# 14_PM8916_CONTROL_CLOCK.net
KiCad netlist of a schematic drawn in Altium Designer
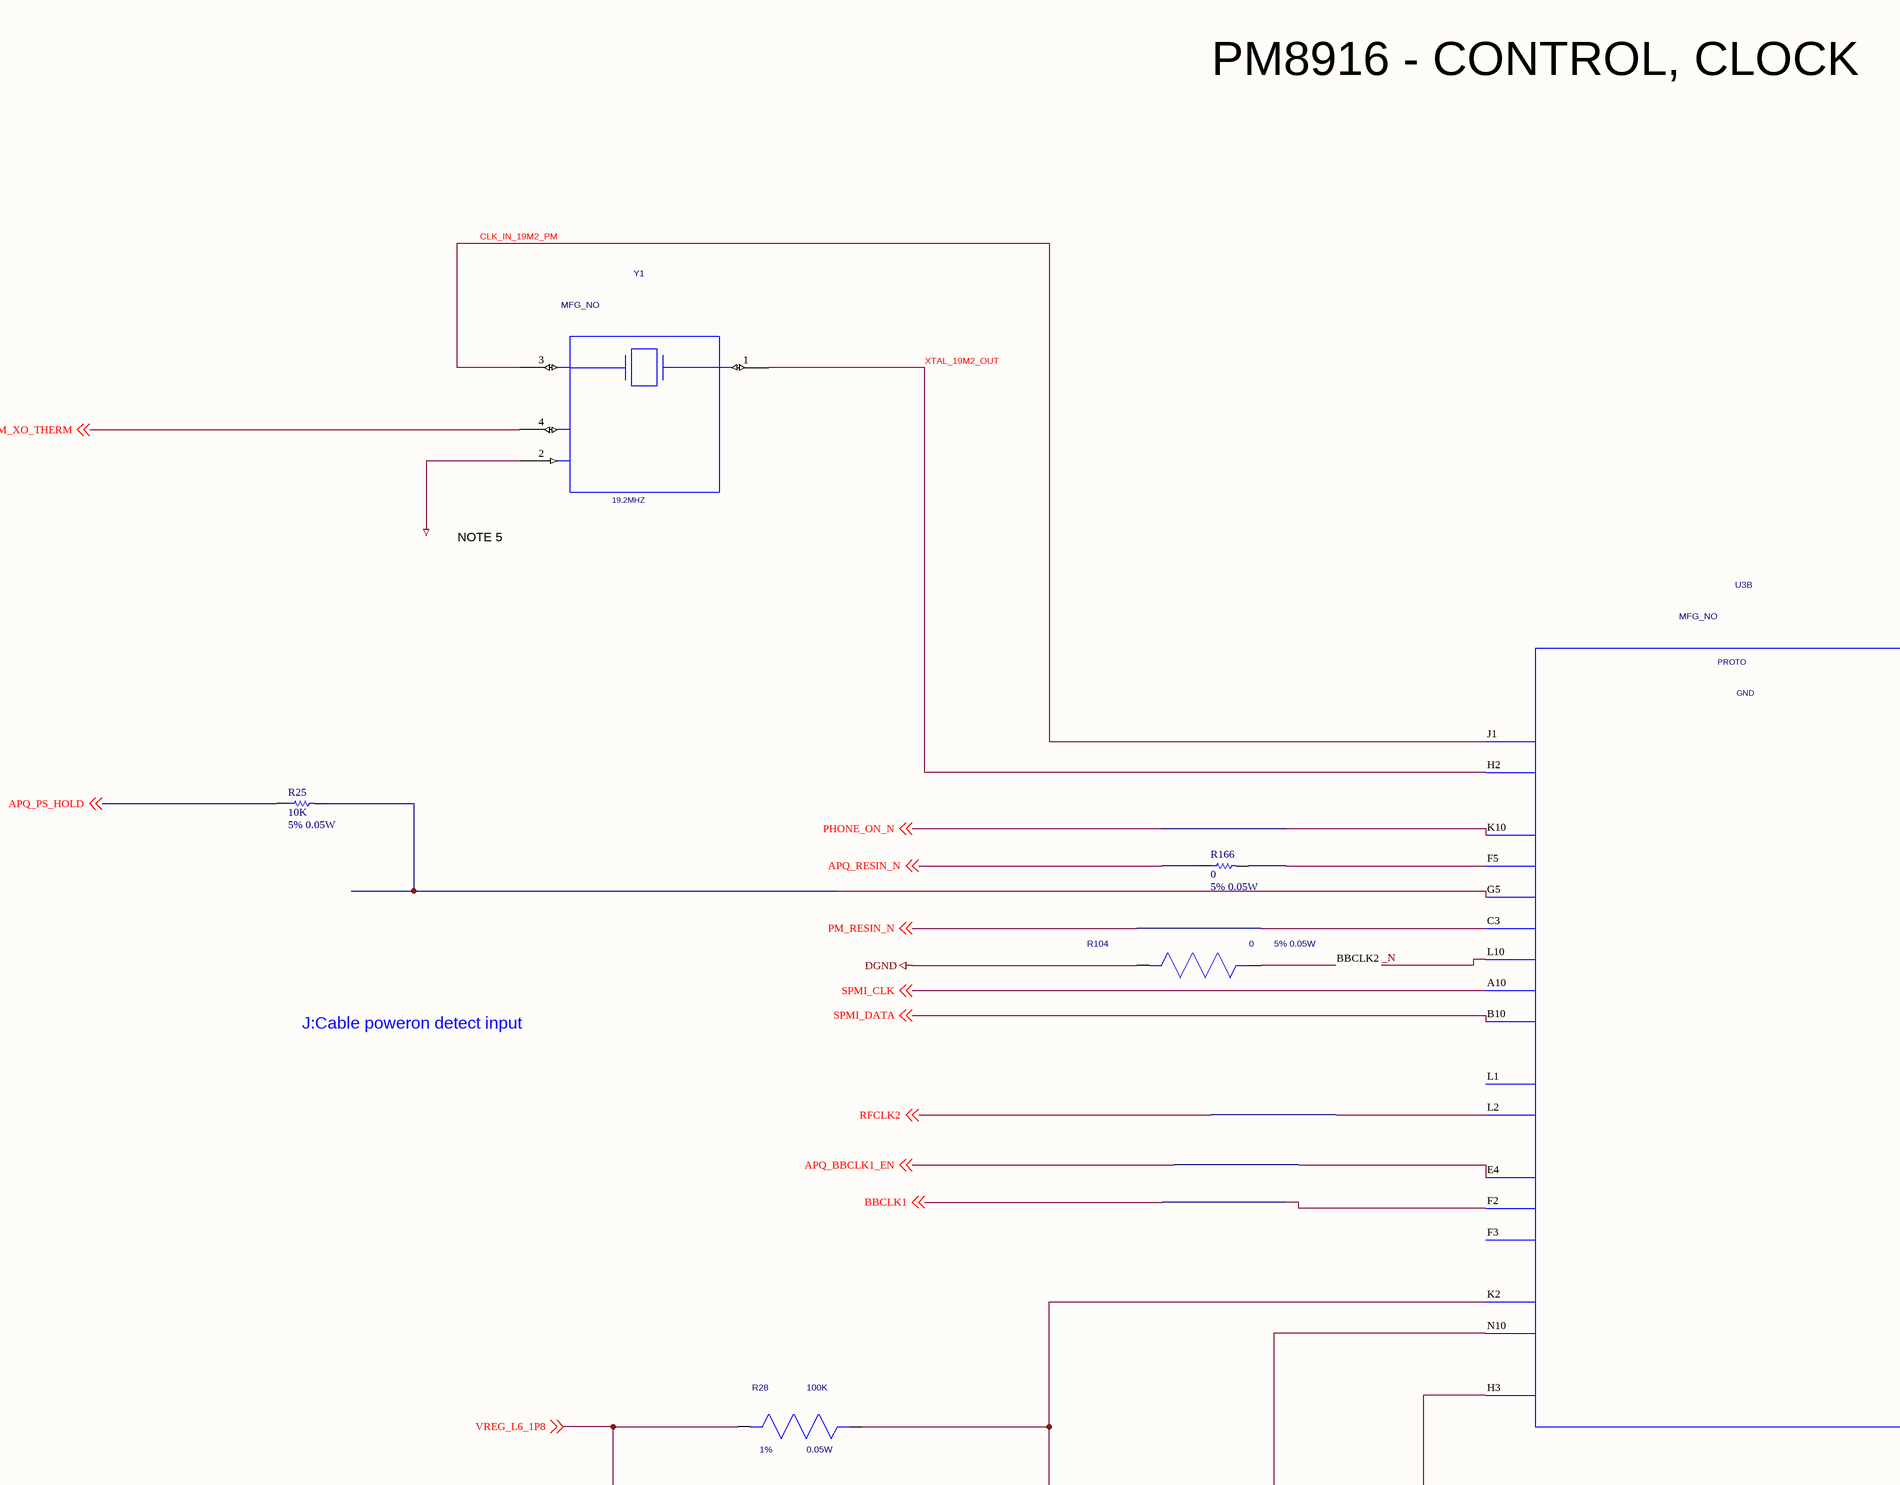
[diagram p0: 14 PM8916_CONTROL CLOCK.SchDoc, top left]
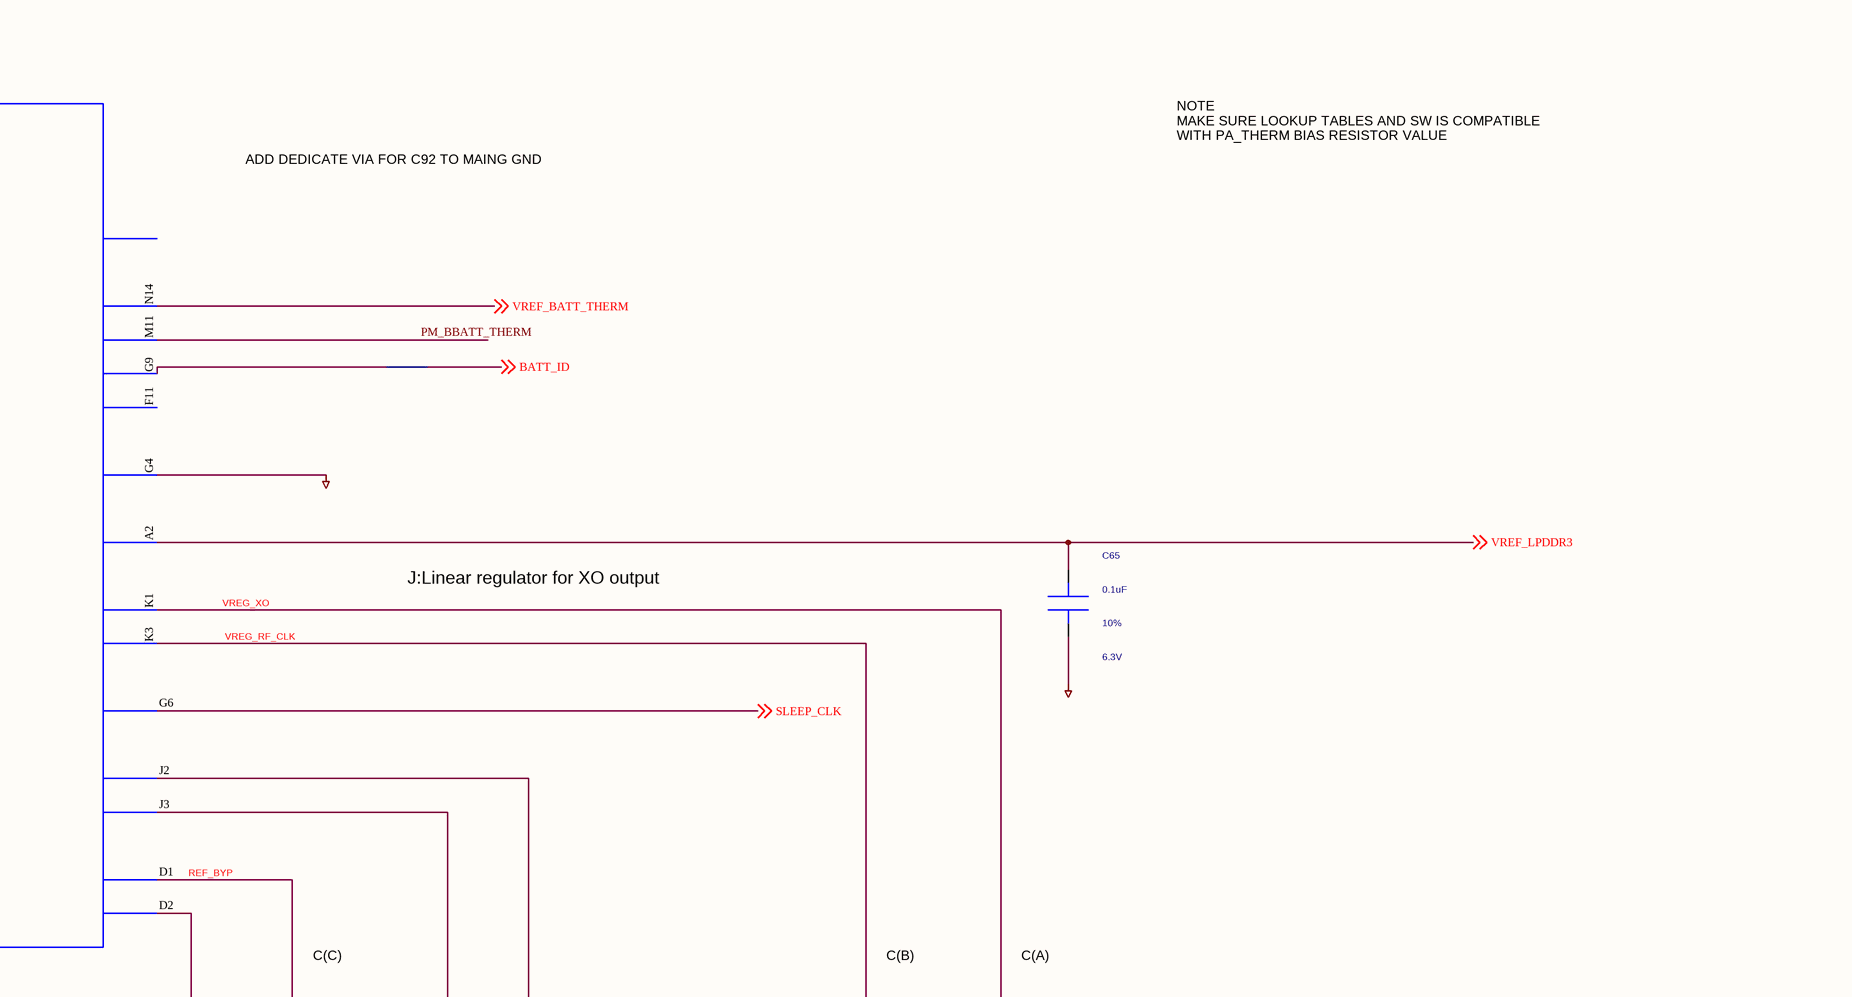
[diagram p1: 14 PM8916_CONTROL CLOCK.SchDoc, top right]
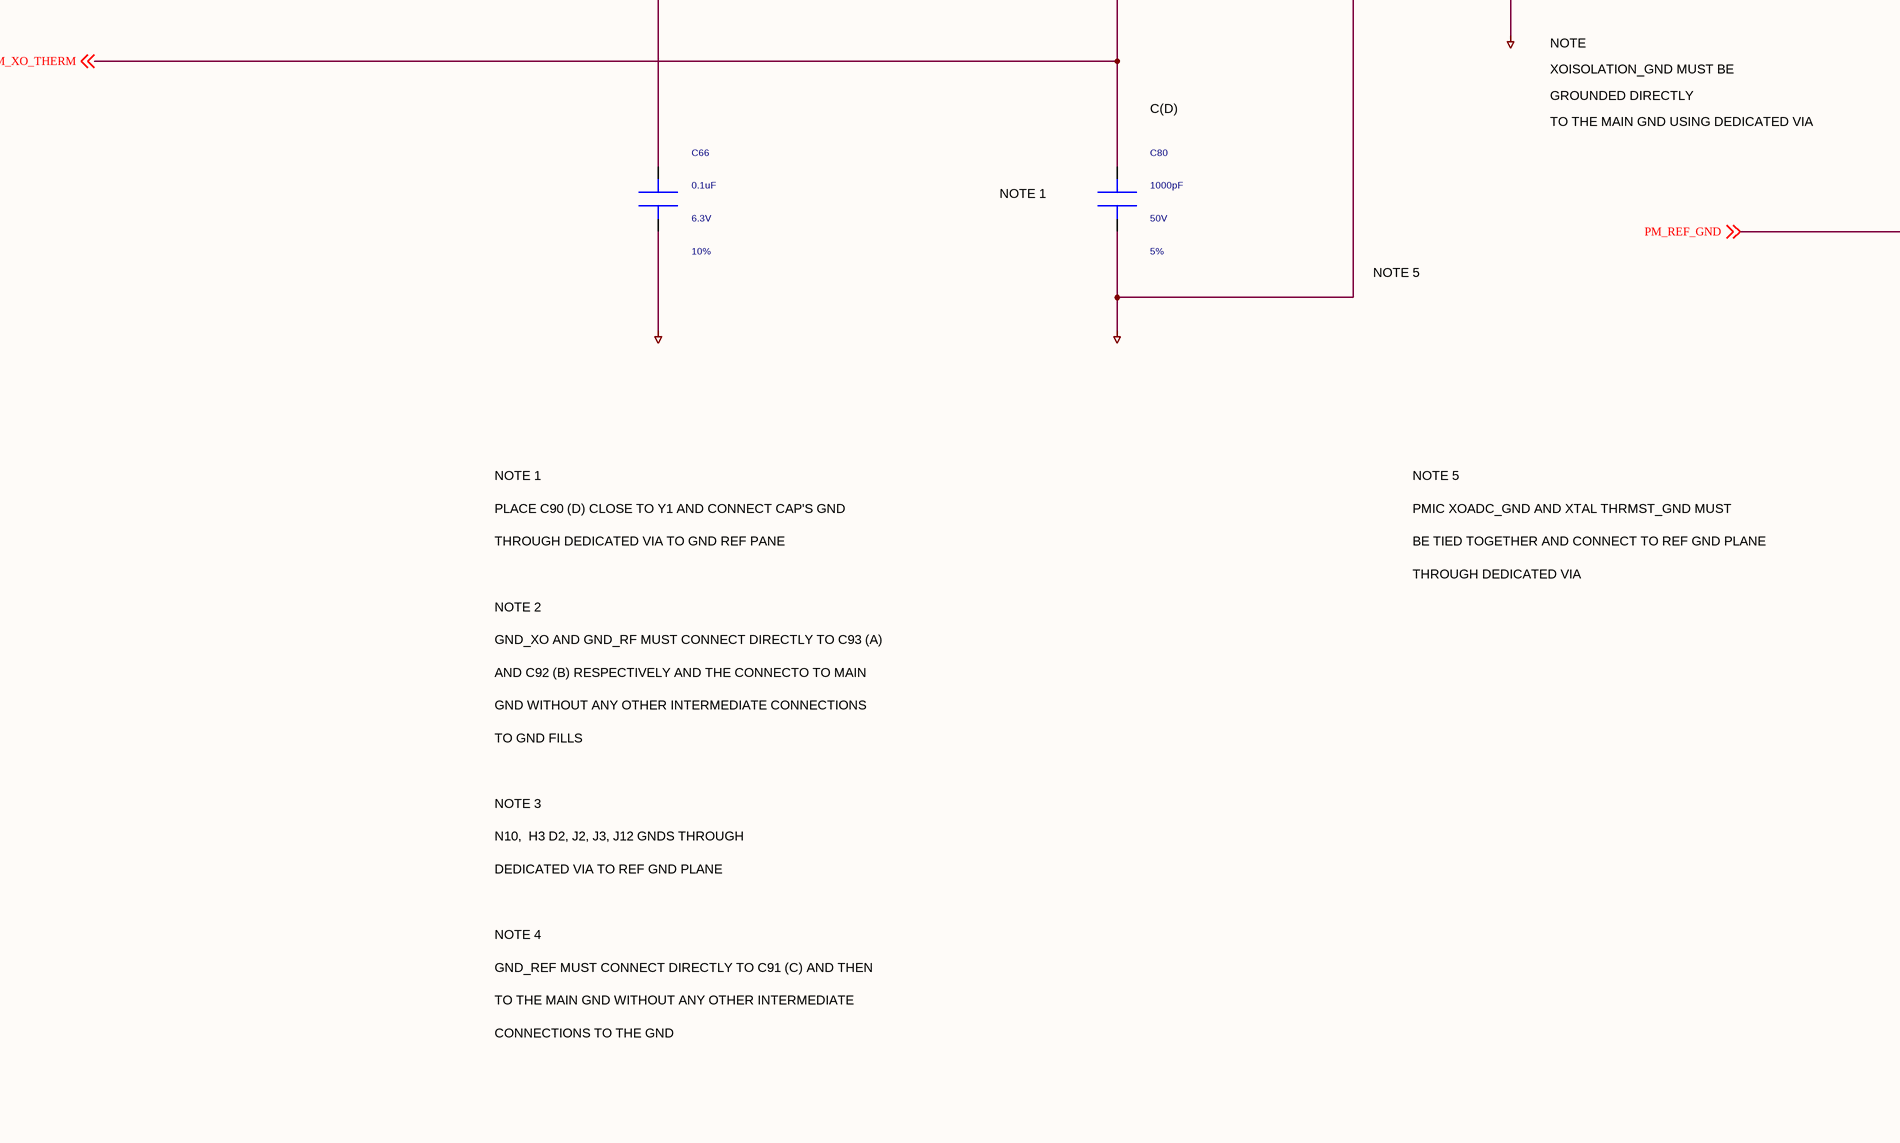
[diagram p2: 14 PM8916_CONTROL CLOCK.SchDoc, bottom left]
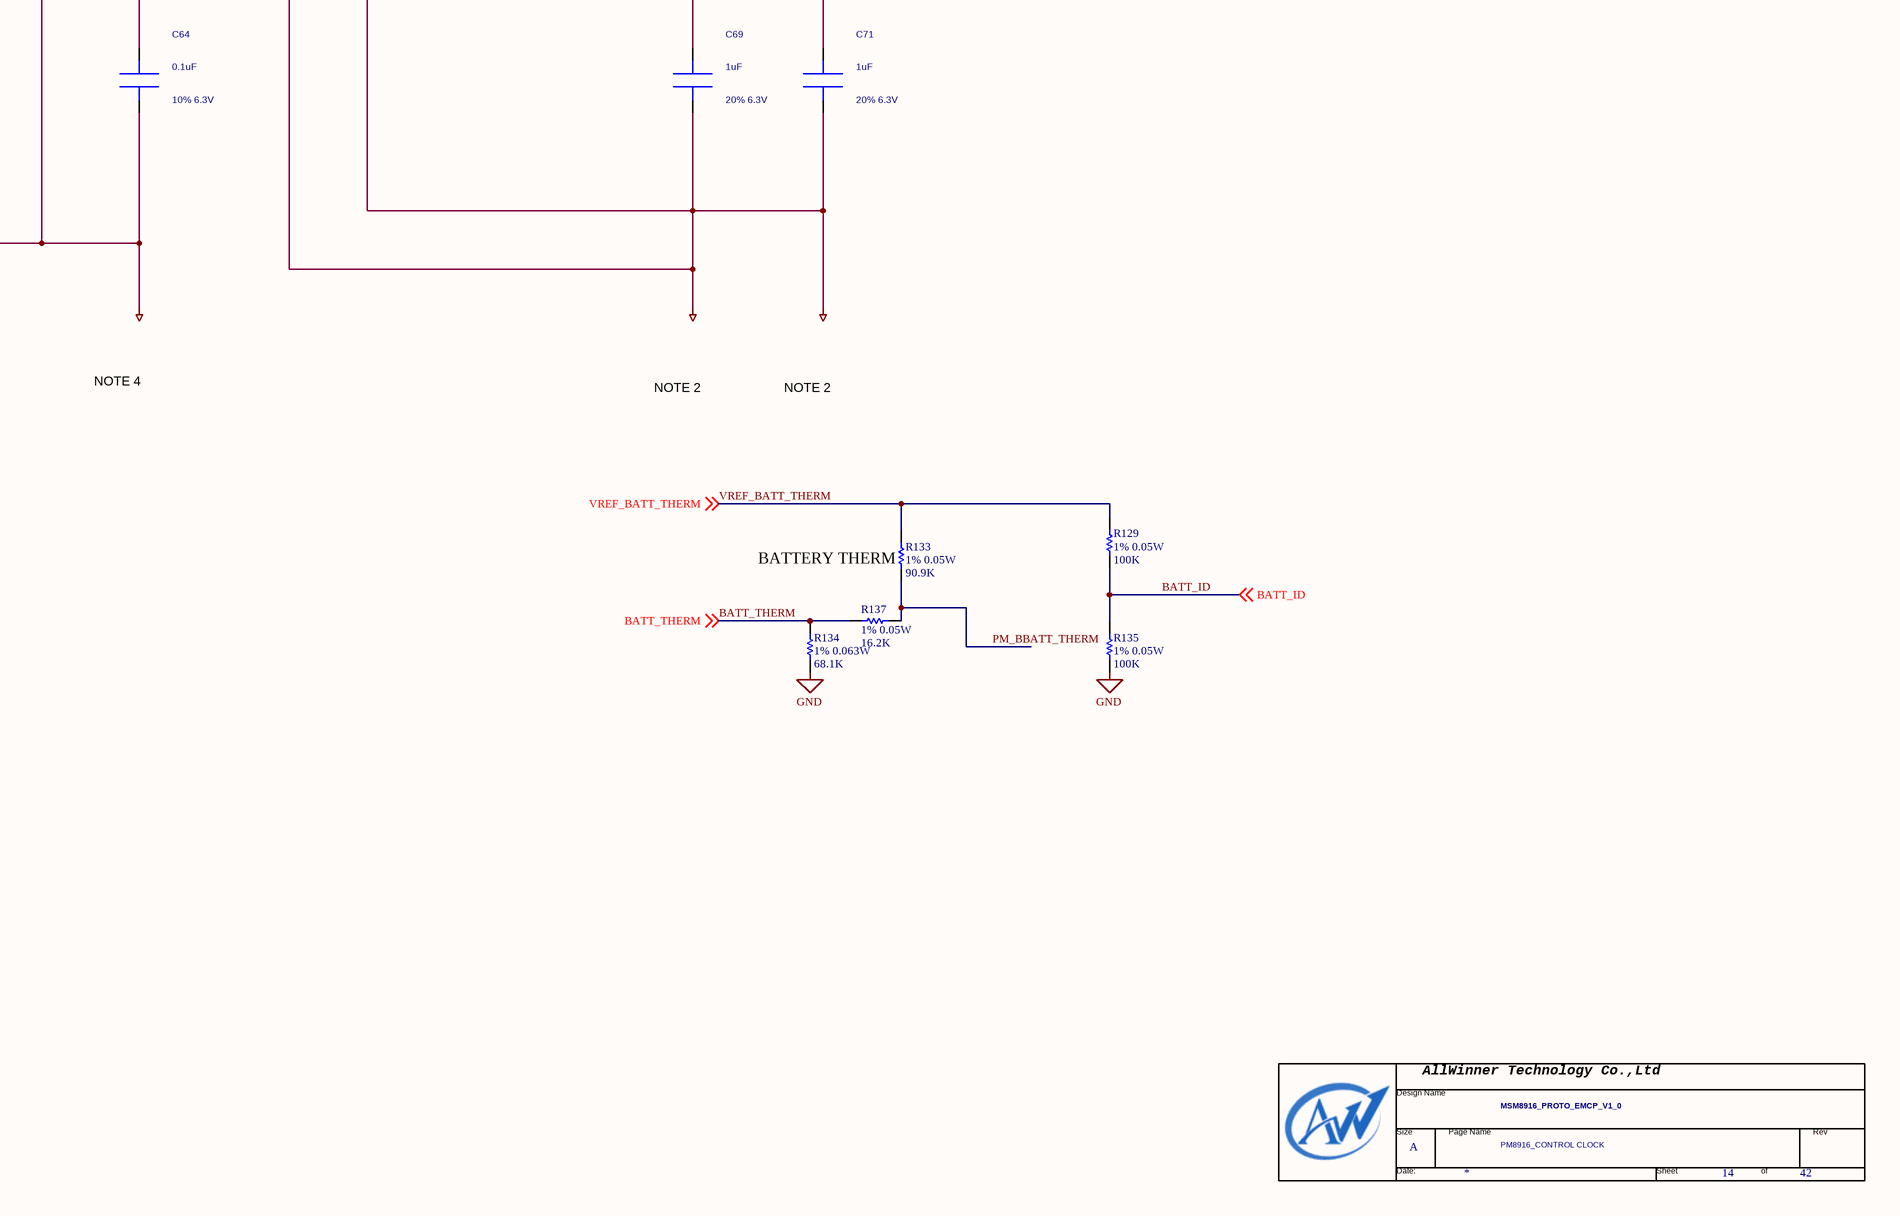
[diagram p3: 14 PM8916_CONTROL CLOCK.SchDoc, bottom right]

(export (version "E")
  (design (tool "Eeschema 10.0.6"))
  (components
    (comp (ref "C64")
      (value "0.1uF")
      (footprint "c0402")
      (fields (field (name "TOLERANCE") "10% 6.3V") (field (name "PART_NUMBER") "MCN_NO"))
      (libsource (lib "MSM8916_DRAM_PMIC_REF_Library") (part "CAP"))
    )
    (comp (ref "C65")
      (value "0.1uF")
      (footprint "c0402")
      (fields
        (field (name "VOLT") "6.3V")
        (field (name "TOLERANCE") "10%")
        (field (name "PART_NUMBER") "MCN_NO")
      )
      (libsource (lib "MSM8916_DRAM_PMIC_REF_Library") (part "CAP"))
    )
    (comp (ref "C66")
      (value "0.1uF")
      (footprint "c0402")
      (fields
        (field (name "VOLT") "10%")
        (field (name "TOLERANCE") "6.3V")
        (field (name "PART_NUMBER") "MCN_NO")
      )
      (libsource (lib "MSM8916_DRAM_PMIC_REF_Library") (part "CAP"))
    )
    (comp (ref "C69")
      (value "1uF")
      (footprint "c0402")
      (fields (field (name "TOLERANCE") "20% 6.3V") (field (name "PART_NUMBER") "MCN_NO"))
      (libsource (lib "MSM8916_DRAM_PMIC_REF_Library") (part "CAP"))
    )
    (comp (ref "C71")
      (value "1uF")
      (footprint "c0402")
      (fields (field (name "TOLERANCE") "20% 6.3V") (field (name "PART_NUMBER") "MCN_NO"))
      (libsource (lib "MSM8916_DRAM_PMIC_REF_Library") (part "CAP"))
    )
    (comp (ref "C80")
      (value "1000pF")
      (footprint "c0402")
      (fields
        (field (name "VOLT") "5%")
        (field (name "TOLERANCE") "50V")
        (field (name "PART_NUMBER") "MCN_NO")
      )
      (libsource (lib "MSM8916_DRAM_PMIC_REF_Library") (part "CAP"))
    )
    (comp (ref "R25")
      (value "10K")
      (footprint "r0402")
      (description "Resistor")
      (fields (field (name "ALTIUM_VALUE") "5% 0.05W") (field (name "PUBLISHER") "Altium Limited"))
      (libsource (lib "Miscellaneous Devices") (part "Res1"))
    )
    (comp (ref "R28")
      (value "100K")
      (footprint "c0402")
      (fields
        (field (name "TOLERANCE") "1%")
        (field (name "POWER") "0.05W")
        (field (name "PART_NUMBER") "MCN_NO")
      )
      (libsource (lib "MSM8916_DRAM_PMIC_REF_Library") (part "RESISTOR_Dup3"))
    )
    (comp (ref "R104")
      (value "0")
      (footprint "c0402")
      (fields
        (field (name "TOLERANCE") "?%")
        (field (name "POWER") "5% 0.05W")
        (field (name "PART_NUMBER") "MCN_NO")
      )
      (libsource (lib "MSM8916_DRAM_PMIC_REF_Library") (part "RESISTOR_Dup3"))
    )
    (comp (ref "R129")
      (value "1% 0.05W")
      (footprint "r0402")
      (description "Resistor")
      (fields (field (name "ALTIUM_VALUE") "100K") (field (name "PUBLISHER") "Altium Limited"))
      (libsource (lib "Miscellaneous Devices") (part "Res1"))
    )
    (comp (ref "R133")
      (value "1% 0.05W")
      (footprint "r0402")
      (description "Resistor")
      (fields (field (name "ALTIUM_VALUE") "90.9K") (field (name "PUBLISHER") "Altium Limited"))
      (libsource (lib "Miscellaneous Devices") (part "Res1"))
    )
    (comp (ref "R134")
      (value "1% 0.063W")
      (footprint "r0402")
      (description "Resistor")
      (fields (field (name "ALTIUM_VALUE") "68.1K") (field (name "PUBLISHER") "Altium Limited"))
      (libsource (lib "Miscellaneous Devices") (part "Res1"))
    )
    (comp (ref "R135")
      (value "1% 0.05W")
      (footprint "r0402")
      (description "Resistor")
      (fields (field (name "ALTIUM_VALUE") "100K") (field (name "PUBLISHER") "Altium Limited"))
      (libsource (lib "Miscellaneous Devices") (part "Res1"))
    )
    (comp (ref "R137")
      (value "1% 0.05W")
      (footprint "r0402")
      (description "Resistor")
      (fields (field (name "ALTIUM_VALUE") "16.2K") (field (name "PUBLISHER") "Altium Limited"))
      (libsource (lib "Miscellaneous Devices") (part "Res1"))
    )
    (comp (ref "R166")
      (value "0")
      (footprint "r0402")
      (description "Resistor")
      (fields (field (name "ALTIUM_VALUE") "5% 0.05W") (field (name "PUBLISHER") "Altium Limited"))
      (libsource (lib "Miscellaneous Devices") (part "Res1"))
    )
    (comp (ref "U3")
      (value "ASIC_PM8916")
      (footprint "PM-8916-0-176NSP-TR-00-0")
      (fields
        (field (name "SYMNAME") "GND")
        (field (name "PART_NUMBER") "MCN_NO")
        (field (name "PART_ID") "MFG_NO")
        (field (name "BLOCKID") "PROTO")
      )
      (libsource (lib "MSM8916_DRAM_PMIC_REF_Library") (part "ASIC_PM8916"))
    )
    (comp (ref "Y1")
      (value "crystal_4pin_thermistor_gnd")
      (footprint "c0402")
      (fields
        (field (name "PART_NUMBER") "MCN_NO")
        (field (name "PART_ID") "MFG_NO")
        (field (name "FREQ") "19.2MHZ")
      )
      (libsource (lib "MSM8916_DRAM_PMIC_REF_Library") (part "CRYSTAL_4PIN_THERMISTOR_GND"))
    )
  )
  (nets
    (net (code "1") (name "/CBLPWR_N") (class "Default")
      (node (ref "R104") (pin "2") (pinfunction "NEG_2") (pintype "bidirectional"))
      (node (ref "U3") (pin "L10") (pinfunction "CBLPWR*_L10") (pintype "bidirectional"))
    )
    (net (code "2") (name "/CLK_IN_19M2_PM") (class "Default")
      (node (ref "U3") (pin "J1") (pinfunction "XTAL19M2_IN_J1") (pintype "bidirectional"))
      (node (ref "Y1") (pin "3") (pinfunction "H2_3") (pintype "bidirectional"))
    )
    (net (code "3") (name "/PM_BBATT_THERM") (class "Default")
      (node (ref "R133") (pin "1") (pinfunction "1_1") (pintype "passive"))
      (node (ref "R137") (pin "2") (pinfunction "2_2") (pintype "passive"))
      (node (ref "U3") (pin "M11") (pinfunction "BAT_THERM_M11") (pintype "bidirectional"))
    )
    (net (code "4") (name "/REF_BYP") (class "Default")
      (node (ref "C64") (pin "1") (pinfunction "POS_1") (pintype "bidirectional"))
      (node (ref "U3") (pin "D1") (pinfunction "REF_BYP_D1") (pintype "bidirectional"))
    )
    (net (code "5") (name "/VREG_RF_CLK") (class "Default")
      (node (ref "C69") (pin "1") (pinfunction "POS_1") (pintype "bidirectional"))
      (node (ref "U3") (pin "K3") (pinfunction "VREG_RF_CLK_K3") (pintype "bidirectional"))
    )
    (net (code "6") (name "/VREG_XO") (class "Default")
      (node (ref "C71") (pin "1") (pinfunction "POS_1") (pintype "bidirectional"))
      (node (ref "U3") (pin "K1") (pinfunction "VREG_XO_K1") (pintype "bidirectional"))
    )
    (net (code "7") (name "/XTAL_19M2_OUT") (class "Default")
      (node (ref "U3") (pin "H2") (pinfunction "XTAL19M2_OUT_H2") (pintype "bidirectional"))
      (node (ref "Y1") (pin "1") (pinfunction "H1_1") (pintype "bidirectional"))
    )
    (net (code "8") (name "APQ_BBCLK1_EN") (class "Default")
      (node (ref "U3") (pin "E4") (pinfunction "BBCLK1_EN_E4") (pintype "bidirectional"))
    )
    (net (code "9") (name "APQ_PS_HOLD") (class "Default")
      (node (ref "R25") (pin "1") (pinfunction "1_1") (pintype "passive"))
    )
    (net (code "10") (name "APQ_RESIN_N") (class "Default")
      (node (ref "R166") (pin "1") (pinfunction "1_1") (pintype "passive"))
    )
    (net (code "11") (name "AVDD_BYP") (class "Default")
      (node (ref "U3") (pin "C2") (pinfunction "AVDD_BYP_C2") (pintype "power_in"))
    )
    (net (code "12") (name "BATT_ID") (class "Default")
      (node (ref "R129") (pin "1") (pinfunction "1_1") (pintype "passive"))
      (node (ref "R135") (pin "2") (pinfunction "2_2") (pintype "passive"))
      (node (ref "U3") (pin "G9") (pinfunction "BAT_ID_G9") (pintype "bidirectional"))
    )
    (net (code "13") (name "BATT_THERM") (class "Default")
      (node (ref "R134") (pin "2") (pinfunction "2_2") (pintype "passive"))
      (node (ref "R137") (pin "1") (pinfunction "1_1") (pintype "passive"))
    )
    (net (code "14") (name "BBCLK1") (class "Default")
      (node (ref "U3") (pin "F2") (pinfunction "BBCLK1_F2") (pintype "bidirectional"))
    )
    (net (code "15") (name "DGND") (class "Default")
      (node (ref "C64") (pin "2") (pinfunction "NEG_2") (pintype "bidirectional"))
      (node (ref "C65") (pin "2") (pinfunction "NEG_2") (pintype "bidirectional"))
      (node (ref "C66") (pin "2") (pinfunction "NEG_2") (pintype "bidirectional"))
      (node (ref "C69") (pin "2") (pinfunction "NEG_2") (pintype "bidirectional"))
      (node (ref "C71") (pin "2") (pinfunction "NEG_2") (pintype "bidirectional"))
      (node (ref "C80") (pin "2") (pinfunction "NEG_2") (pintype "bidirectional"))
      (node (ref "R104") (pin "1") (pinfunction "POS_1") (pintype "bidirectional"))
      (node (ref "U3") (pin "D2") (pinfunction "REF_GND_D2") (pintype "input"))
      (node (ref "U3") (pin "G4") (pinfunction "TEST_EN_G4") (pintype "bidirectional"))
      (node (ref "U3") (pin "H3") (pinfunction "XOISOLATION_GND_H3") (pintype "input"))
      (node (ref "U3") (pin "J2") (pinfunction "GND_XO_J2") (pintype "input"))
      (node (ref "U3") (pin "J3") (pinfunction "GND_RF_J3") (pintype "input"))
      (node (ref "U3") (pin "N10") (pinfunction "XOADC_GND_N10") (pintype "input"))
      (node (ref "Y1") (pin "2") (pinfunction "THRMSTR_GND_2") (pintype "input"))
    )
    (net (code "16") (name "GND") (class "Default")
      (node (ref "R134") (pin "1") (pinfunction "1_1") (pintype "passive"))
      (node (ref "R135") (pin "1") (pinfunction "1_1") (pintype "passive"))
    )
    (net (code "17") (name "Net-(U3B-PON_RESET*)") (class "Default")
      (node (ref "R166") (pin "2") (pinfunction "2_2") (pintype "passive"))
      (node (ref "U3") (pin "F5") (pinfunction "PON_RESET*_F5") (pintype "bidirectional"))
    )
    (net (code "18") (name "Net-(U3B-PS_HOLD)") (class "Default")
      (node (ref "R25") (pin "2") (pinfunction "2_2") (pintype "passive"))
      (node (ref "U3") (pin "G5") (pinfunction "PS_HOLD_G5") (pintype "bidirectional"))
    )
    (net (code "19") (name "PHONE_ON_N") (class "Default")
      (node (ref "U3") (pin "K10") (pinfunction "KYPDPWR*_K10") (pintype "bidirectional"))
    )
    (net (code "20") (name "PM_RESIN_N") (class "Default")
      (node (ref "U3") (pin "C3") (pinfunction "RESIN*_C3") (pintype "bidirectional"))
    )
    (net (code "21") (name "PM_XO_THERM") (class "Default")
      (node (ref "C80") (pin "1") (pinfunction "POS_1") (pintype "bidirectional"))
      (node (ref "R28") (pin "2") (pinfunction "NEG_2") (pintype "bidirectional"))
      (node (ref "U3") (pin "K2") (pinfunction "XO_THERM_K2") (pintype "bidirectional"))
      (node (ref "Y1") (pin "4") (pinfunction "THRMSTR_4") (pintype "bidirectional"))
    )
    (net (code "22") (name "RFCLK2") (class "Default")
      (node (ref "U3") (pin "L2") (pinfunction "RFCLK2_L2") (pintype "bidirectional"))
    )
    (net (code "23") (name "SLEEP_CLK") (class "Default")
      (node (ref "U3") (pin "G6") (pinfunction "SLEEP_CLK1_G6") (pintype "bidirectional"))
    )
    (net (code "24") (name "SPMI_CLK") (class "Default")
      (node (ref "U3") (pin "A10") (pinfunction "SPMI_CLK_A10") (pintype "bidirectional"))
    )
    (net (code "25") (name "SPMI_DATA") (class "Default")
      (node (ref "U3") (pin "B10") (pinfunction "SPMI_DATA_B10") (pintype "bidirectional"))
    )
    (net (code "26") (name "VREF_BATT_THERM") (class "Default")
      (node (ref "R129") (pin "2") (pinfunction "2_2") (pintype "passive"))
      (node (ref "R133") (pin "2") (pinfunction "2_2") (pintype "passive"))
      (node (ref "U3") (pin "N14") (pinfunction "VREF_BAT_THERM_N14") (pintype "bidirectional"))
    )
    (net (code "27") (name "VREF_LPDDR3") (class "Default")
      (node (ref "C65") (pin "1") (pinfunction "POS_1") (pintype "bidirectional"))
      (node (ref "U3") (pin "A2") (pinfunction "VREF_LPDDR2_A2") (pintype "bidirectional"))
    )
    (net (code "28") (name "VREG_L6_1P8") (class "Default")
      (node (ref "C66") (pin "1") (pinfunction "POS_1") (pintype "bidirectional"))
      (node (ref "R28") (pin "1") (pinfunction "POS_1") (pintype "bidirectional"))
    )
    (net (code "29") (name "unconnected-(U3B-BBCLK2-PadF3)") (class "Default")
      (node (ref "U3") (pin "F3") (pinfunction "BBCLK2_F3") (pintype "bidirectional"))
    )
    (net (code "30") (name "unconnected-(U3B-PA_THERM-PadF11)") (class "Default")
      (node (ref "U3") (pin "F11") (pinfunction "PA_THERM_F11") (pintype "bidirectional"))
    )
    (net (code "31") (name "unconnected-(U3B-RFCLK1-PadL1)") (class "Default")
      (node (ref "U3") (pin "L1") (pinfunction "RFCLK1_L1") (pintype "bidirectional"))
    )
  )
)
